# MP8756GD_2.net
KiCad netlist of a schematic drawn in Altium Designer
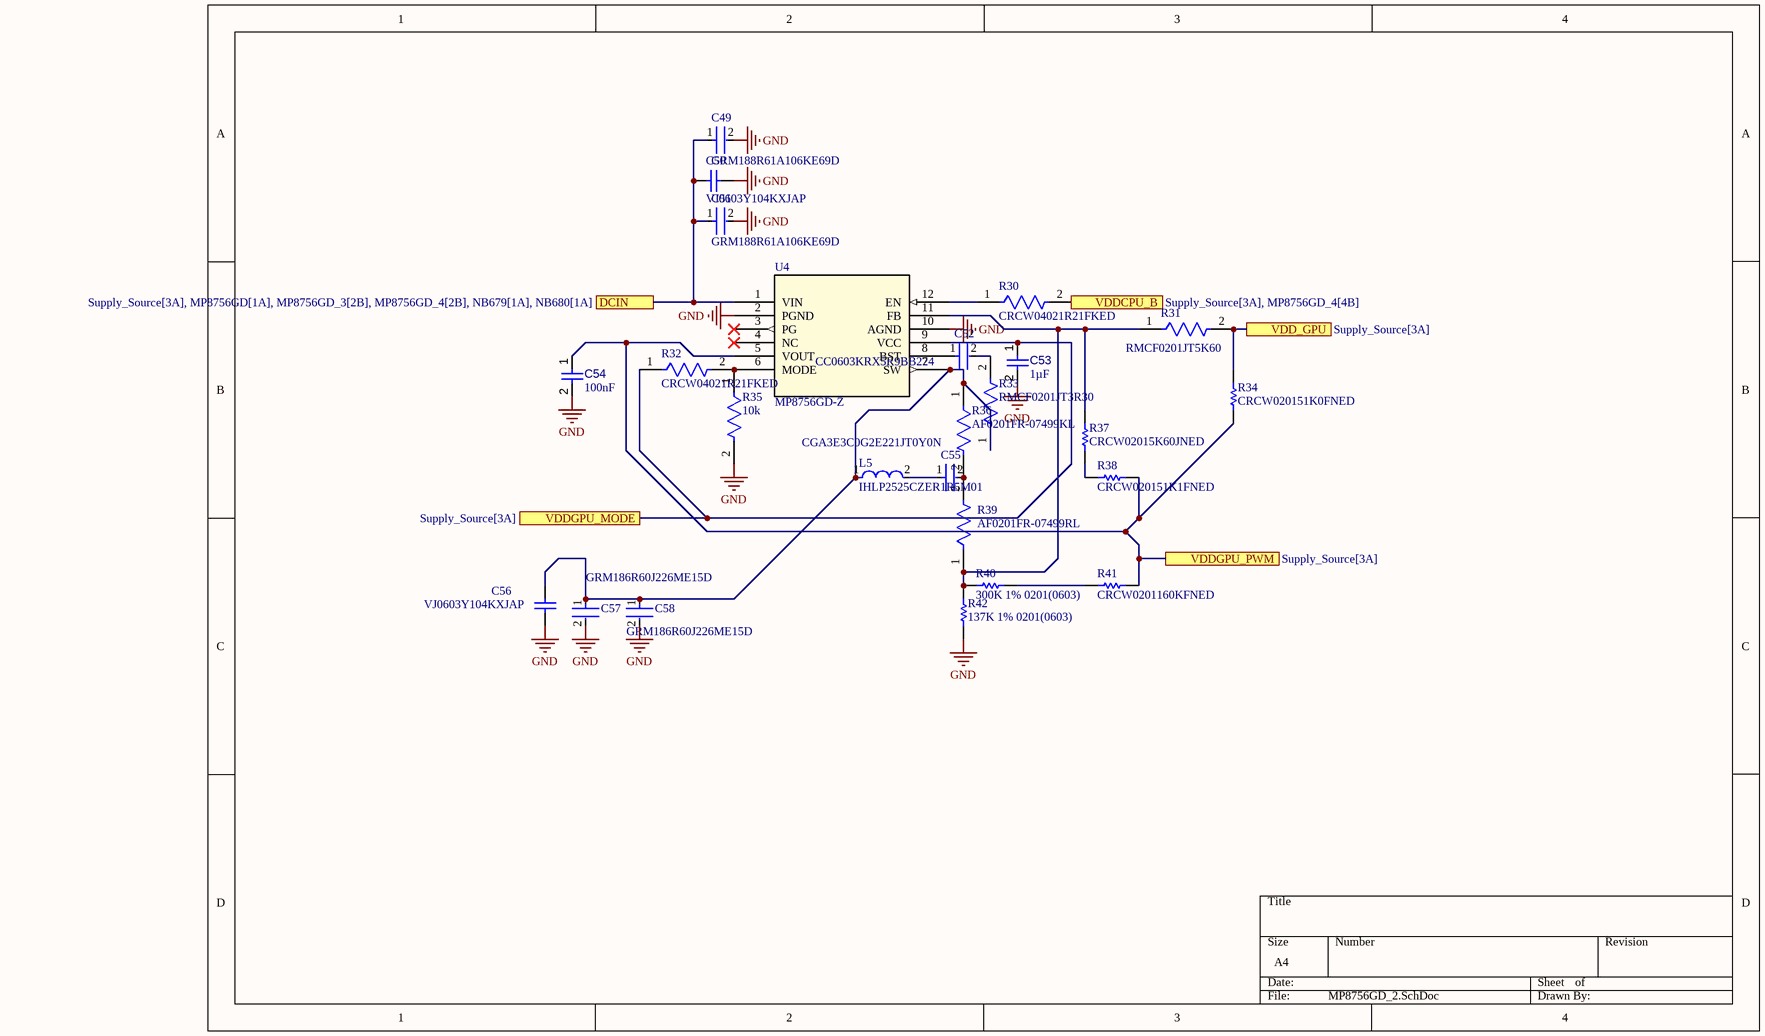
[diagram p0: MP8756GD_2.SchDoc]

(export (version "E")
  (design (tool "Eeschema 10.0.6"))
  (components
    (comp (ref "C49")
      (value "GRM188R61A106KE69D")
      (footprint "FP-GRM18-0_15-MFG")
      (description "CAP CER 10UF 10V X5R 0603")
      (fields
        (field (name "OCTOPART") "https://octopart.com/grm188r61a106ke69d-murata-22851381")
        (field (name "MANUFACTURER") "Murata")
      )
      (libsource (lib "Altium Content Vault") (part "11868f565c42a9108669ba33697ecf6"))
    )
    (comp (ref "C50")
      (value "VJ0603Y104KXJAP")
      (footprint "CAPC1608X92X38NL15T08")
      (fields (field (name "MANUFACTURER") "Vitramon"))
      (libsource (lib "Altium Content Vault") (part "CAP"))
    )
    (comp (ref "C51")
      (value "GRM188R61A106KE69D")
      (footprint "FP-GRM18-0_15-MFG")
      (description "CAP CER 10UF 10V X5R 0603")
      (fields
        (field (name "OCTOPART") "https://octopart.com/grm188r61a106ke69d-murata-22851381")
        (field (name "MANUFACTURER") "Murata")
      )
      (libsource (lib "Altium Content Vault") (part "11868f565c42a9108669ba33697ecf6"))
    )
    (comp (ref "C52")
      (value "CC0603KRX5R9BB224")
      (footprint "FP-CC0603-DA-MFG")
      (description "CC0603 220 nF X5R 10.00% 50 V")
      (fields
        (field (name "TOLERANCE") "0.1")
        (field (name "OCTOPART") "https://octopart.com/cc0603krx5r9bb224-yageo-90326743")
      )
      (libsource (lib "Altium Content Vault") (part "11868f565c42a9108669ba33697ecf6"))
    )
    (comp (ref "C53")
      (value "1µF")
      (footprint "CAPC1005X55X25LL05T10")
      (description "Chip Capacitor, 1 uF, +/- 10%, 6.3 V, 0402 (1005 Metric)")
      (fields (field (name "TOLERANCE") "10%") (field (name "Comment") "Capacitor 1 uF +/- 10% 6.3 V 0402"))
      (libsource (lib "MIGUEL ANGEL ALVAREZ GUZMAN") (part "CAP-NP-2"))
    )
    (comp (ref "C54")
      (value "100nF")
      (footprint "CAPC1005X56X25LL10T15")
      (description "Chip Capacitor, 0.1 uF, +/- 5%, 16 V, 0402 (1005 Metric)")
      (fields (field (name "TOLERANCE") "5%") (field (name "Comment") "Capacitor 0.1 uF +/- 5% 16 V 0402"))
      (libsource (lib "MIGUEL ANGEL ALVAREZ GUZMAN") (part "CAP-NP-2"))
    )
    (comp (ref "C55")
      (value "CGA3E3C0G2E221JT0Y0N")
      (footprint "FP-CGA3E-0_3-0_1-IPC_B")
      (description "Cap Ceramic 220pF 250V C0G 5% Pad SMD 0603 +125°C Automotive T/R")
      (libsource (lib "Altium Content Vault") (part "b4654b650e69147ec39a6b967a45e02"))
    )
    (comp (ref "C56")
      (value "VJ0603Y104KXJAP")
      (footprint "CAPC1608X92X38NL15T08")
      (fields (field (name "MANUFACTURER") "Vitramon"))
      (libsource (lib "Altium Content Vault") (part "CAP"))
    )
    (comp (ref "C57")
      (value "GRM186R60J226ME15D")
      (footprint "FP-GRM186-0_2-IPC_B")
      (description "Chip Multilayer Ceramic Capacitors for General Purpose, 0603, 22uF, X5R, 15%, 20%, 6.3V")
      (fields (field (name "TOLERANCE") "20%"))
      (libsource (lib "Altium Content Vault") (part "02cd4be3c70576c341d710602a673aa"))
    )
    (comp (ref "C58")
      (value "GRM186R60J226ME15D")
      (footprint "FP-GRM186-0_2-IPC_B")
      (description "Chip Multilayer Ceramic Capacitors for General Purpose, 0603, 22uF, X5R, 15%, 20%, 6.3V")
      (fields (field (name "TOLERANCE") "20%"))
      (libsource (lib "Altium Content Vault") (part "02cd4be3c70576c341d710602a673aa"))
    )
    (comp (ref "L5")
      (value "IHLP2525CZER1R5M01")
      (footprint "FP-IHLP-2525CZ-FP_2_413x3-MFG")
      (description "Commercial Inductors, High Saturation Series 1.5uH 9A 15mΩ 20%")
      (fields (field (name "TOLERANCE") "20%"))
      (libsource (lib "Altium Content Vault") (part "725321dda6339637d4d059423bc1c3c"))
    )
    (comp (ref "R30")
      (value "CRCW04021R21FKED")
      (footprint "FP-CRCW0402-e3-MFG")
      (description "RES Thick Film, 1.21Ω, 1%, 0.063W, 100ppm/°C, 0402")
      (fields (field (name "TOLERANCE") "1%"))
      (libsource (lib "Altium Content Vault") (part "1029c3af85768c4190bb7ad29bc67b5"))
    )
    (comp (ref "R31")
      (value "RMCF0201JT5K60")
      (footprint "FP-RMCF0201-MFG")
      (description "5.6kΩ ±5% 0.05W 0201 Thick Film Chip Resistor AEC-Q200 compliant")
      (fields (field (name "TOLERANCE") "5%"))
      (libsource (lib "Altium Content Vault") (part "1029c3af85768c4190bb7ad29bc67b5"))
    )
    (comp (ref "R32")
      (value "CRCW04021R21FKED")
      (footprint "FP-CRCW0402-e3-MFG")
      (description "RES Thick Film, 1.21Ω, 1%, 0.063W, 100ppm/°C, 0402")
      (fields (field (name "TOLERANCE") "1%"))
      (libsource (lib "Altium Content Vault") (part "1029c3af85768c4190bb7ad29bc67b5"))
    )
    (comp (ref "R33")
      (value "RMCF0201JT3R30")
      (footprint "FP-RMCF0201-IPC_A")
      (description "3.3Ω ±5% 0.05W 0201 Thick Film Chip Resistor AEC-Q200 compliant")
      (fields (field (name "TOLERANCE") "5%"))
      (libsource (lib "Altium Content Vault") (part "1029c3af85768c4190bb7ad29bc67b5"))
    )
    (comp (ref "R34")
      (value "CRCW020151K0FNED")
      (footprint "RESC0603X28X15LL05T05")
      (fields (field (name "MANUFACTURER") "Vishay Dale"))
      (libsource (lib "Altium Content Vault") (part "RES"))
    )
    (comp (ref "R35")
      (value "10k")
      (footprint "FP-RT0201-IPC_C")
      (description "Fixed Resistor, Thin Film, 0.05W, 10000ohm, 25V, 0.1% +/-Tol, 50ppm/Cel, Surface Mount, 0201")
      (fields (field (name "TOLERANCE") "0.1%") (field (name "Comment") "RT0201BRE0710KL"))
      (libsource (lib "MIGUEL ANGEL ALVAREZ GUZMAN") (part "1029c3af85768c4190bb7ad29bc67b5"))
    )
    (comp (ref "R36")
      (value "AF0201FR-07499KL")
      (footprint "FP-AF0201-MFG")
      (description "Anti-Sulfurated Chip Resistors Automotive Grade 499kΩ 1% 200ppm/°C 0201")
      (fields (field (name "TOLERANCE") "1%"))
      (libsource (lib "Altium Content Vault") (part "1029c3af85768c4190bb7ad29bc67b5"))
    )
    (comp (ref "R37")
      (value "CRCW02015K60JNED")
      (footprint "RESC0603X28X15NL05T05")
      (fields (field (name "MANUFACTURER") "Vishay Dale"))
      (libsource (lib "Altium Content Vault") (part "RES"))
    )
    (comp (ref "R38")
      (value "CRCW020151K1FNED")
      (footprint "RESC0603X28X15ML05T05")
      (fields (field (name "MANUFACTURER") "Vishay Dale"))
      (libsource (lib "Altium Content Vault") (part "RES"))
    )
    (comp (ref "R39")
      (value "AF0201FR-07499RL")
      (footprint "FP-AF0201-IPC_A")
      (description "Anti-Sulfurated Chip Resistors Automotive Grade 499Ω 1% 200ppm/°C 0201")
      (fields (field (name "TOLERANCE") "1%"))
      (libsource (lib "Altium Content Vault") (part "1029c3af85768c4190bb7ad29bc67b5"))
    )
    (comp (ref "R40")
      (value "300K 1% 0201(0603)")
      (footprint "RESC0201(0603)_L")
      (description "300K 0.05W 1% 0201 (0603 Metric)  SMD")
      (fields (field (name "POWER") "0.05 W") (field (name "TOLERANCE") "1 %"))
      (libsource (lib "Altium Content Vault") (part "RES"))
    )
    (comp (ref "R41")
      (value "CRCW0201160KFNED")
      (footprint "RESC0603X28X15ML05T05")
      (fields (field (name "MANUFACTURER") "Vishay Dale"))
      (libsource (lib "Altium Content Vault") (part "RES"))
    )
    (comp (ref "R42")
      (value "137K 1% 0201(0603)")
      (footprint "RESC0201(0603)_M")
      (description "137K 0.05W 1% 0201 (0603 Metric)  SMD")
      (fields (field (name "POWER") "0.05 W") (field (name "TOLERANCE") "1 %"))
      (libsource (lib "Altium Content Vault") (part "RES"))
    )
    (comp (ref "U4")
      (value "MP8756GD-Z")
      (footprint "QFN-12_MP8756_MNP")
      (description "26V 6A Low IQ High-Current Synchronous Step-Down Converter")
      (fields (field (name "COPYRIGHT") "Copyright (C) 2025 Ultra Librarian. All rights reserved."))
      (libsource (lib "MIGUEL ANGEL ALVAREZ GUZMAN") (part "MP8756GD-Z"))
    )
  )
  (nets
    (net (code "1") (name "/DCIN") (class "Default")
      (node (ref "C49") (pin "1") (pinfunction "1_1") (pintype "passive"))
      (node (ref "C50") (pin "2") (pinfunction "2_2") (pintype "passive"))
      (node (ref "C51") (pin "1") (pinfunction "1_1") (pintype "passive"))
      (node (ref "U4") (pin "1") (pinfunction "VIN_1") (pintype "power_in"))
    )
    (net (code "2") (name "/VDDCPU_B") (class "Default")
      (node (ref "R30") (pin "2") (pinfunction "2_2") (pintype "passive"))
    )
    (net (code "3") (name "/VDDGPU_MODE") (class "Default")
      (node (ref "C53") (pin "1") (pinfunction "1_1") (pintype "passive"))
      (node (ref "R32") (pin "1") (pinfunction "1_1") (pintype "passive"))
      (node (ref "U4") (pin "9") (pinfunction "VCC_9") (pintype "power_in"))
    )
    (net (code "4") (name "/VDDGPU_PWM") (class "Default")
      (node (ref "C54") (pin "1") (pinfunction "1_1") (pintype "passive"))
      (node (ref "R34") (pin "2") (pinfunction "2_2") (pintype "passive"))
      (node (ref "R38") (pin "2") (pinfunction "2_2") (pintype "passive"))
      (node (ref "R41") (pin "2") (pinfunction "2_2") (pintype "passive"))
      (node (ref "U4") (pin "5") (pinfunction "VOUT_5") (pintype "power_in"))
    )
    (net (code "5") (name "/VDD_GPU") (class "Default")
      (node (ref "R31") (pin "2") (pinfunction "2_2") (pintype "passive"))
      (node (ref "R34") (pin "1") (pinfunction "1_1") (pintype "passive"))
    )
    (net (code "6") (name "GND") (class "Default")
      (node (ref "C49") (pin "2") (pinfunction "2_2") (pintype "passive"))
      (node (ref "C50") (pin "1") (pinfunction "1_1") (pintype "passive"))
      (node (ref "C51") (pin "2") (pinfunction "2_2") (pintype "passive"))
      (node (ref "C53") (pin "2") (pinfunction "2_2") (pintype "passive"))
      (node (ref "C54") (pin "2") (pinfunction "2_2") (pintype "passive"))
      (node (ref "C56") (pin "1") (pinfunction "1_1") (pintype "passive"))
      (node (ref "C57") (pin "2") (pinfunction "2_2") (pintype "passive"))
      (node (ref "C58") (pin "2") (pinfunction "2_2") (pintype "passive"))
      (node (ref "R35") (pin "2") (pinfunction "2_2") (pintype "passive"))
      (node (ref "R42") (pin "1") (pinfunction "1_1") (pintype "passive"))
      (node (ref "U4") (pin "10") (pinfunction "AGND_10") (pintype "power_in"))
      (node (ref "U4") (pin "2") (pinfunction "PGND_2") (pintype "power_in"))
    )
    (net (code "7") (name "Net-(C52-Pad2)") (class "Default")
      (node (ref "C52") (pin "2") (pinfunction "2_2") (pintype "passive"))
      (node (ref "R33") (pin "2") (pinfunction "2_2") (pintype "passive"))
    )
    (net (code "8") (name "Net-(C55-Pad1)") (class "Default")
      (node (ref "C55") (pin "1") (pinfunction "1_1") (pintype "passive"))
      (node (ref "L5") (pin "2") (pinfunction "2_2") (pintype "passive"))
    )
    (net (code "9") (name "Net-(C55-Pad2)") (class "Default")
      (node (ref "C55") (pin "2") (pinfunction "2_2") (pintype "passive"))
      (node (ref "R36") (pin "2") (pinfunction "2_2") (pintype "passive"))
      (node (ref "R39") (pin "2") (pinfunction "2_2") (pintype "passive"))
    )
    (net (code "10") (name "Net-(R37-Pad2)") (class "Default")
      (node (ref "R37") (pin "2") (pinfunction "2_2") (pintype "passive"))
      (node (ref "R38") (pin "1") (pinfunction "1_1") (pintype "passive"))
    )
    (net (code "11") (name "Net-(R40-Pad2)") (class "Default")
      (node (ref "R40") (pin "2") (pinfunction "2_2") (pintype "passive"))
      (node (ref "R41") (pin "1") (pinfunction "1_1") (pintype "passive"))
    )
    (net (code "12") (name "Net-(U4-BST)") (class "Default")
      (node (ref "C52") (pin "1") (pinfunction "1_1") (pintype "passive"))
      (node (ref "U4") (pin "8") (pinfunction "BST_8") (pintype "power_in"))
    )
    (net (code "13") (name "Net-(U4-EN)") (class "Default")
      (node (ref "R30") (pin "1") (pinfunction "1_1") (pintype "passive"))
      (node (ref "U4") (pin "12") (pinfunction "EN_12") (pintype "input"))
    )
    (net (code "14") (name "Net-(U4-FB)") (class "Default")
      (node (ref "R31") (pin "1") (pinfunction "1_1") (pintype "passive"))
      (node (ref "R37") (pin "1") (pinfunction "1_1") (pintype "passive"))
      (node (ref "R39") (pin "1") (pinfunction "1_1") (pintype "passive"))
      (node (ref "R40") (pin "1") (pinfunction "1_1") (pintype "passive"))
      (node (ref "R42") (pin "2") (pinfunction "2_2") (pintype "passive"))
      (node (ref "U4") (pin "11") (pinfunction "FB_11") (pintype "passive"))
    )
    (net (code "15") (name "Net-(U4-MODE)") (class "Default")
      (node (ref "R32") (pin "2") (pinfunction "2_2") (pintype "passive"))
      (node (ref "R35") (pin "1") (pinfunction "1_1") (pintype "passive"))
      (node (ref "U4") (pin "6") (pinfunction "MODE_6") (pintype "passive"))
    )
    (net (code "16") (name "Net-(U4-SW)") (class "Default")
      (node (ref "C56") (pin "2") (pinfunction "2_2") (pintype "passive"))
      (node (ref "C57") (pin "1") (pinfunction "1_1") (pintype "passive"))
      (node (ref "C58") (pin "1") (pinfunction "1_1") (pintype "passive"))
      (node (ref "L5") (pin "1") (pinfunction "1_1") (pintype "passive"))
      (node (ref "R33") (pin "1") (pinfunction "1_1") (pintype "passive"))
      (node (ref "R36") (pin "1") (pinfunction "1_1") (pintype "passive"))
      (node (ref "U4") (pin "7") (pinfunction "SW_7") (pintype "output"))
    )
    (net (code "17") (name "unconnected-(U4-NC-Pad4)") (class "Default")
      (node (ref "U4") (pin "4") (pinfunction "NC_4") (pintype "passive+no_connect"))
    )
    (net (code "18") (name "unconnected-(U4-PG-Pad3)") (class "Default")
      (node (ref "U4") (pin "3") (pinfunction "PG_3") (pintype "output+no_connect"))
    )
  )
)
